# ucurrent.net
KiCad netlist of a schematic drawn in EAGLE
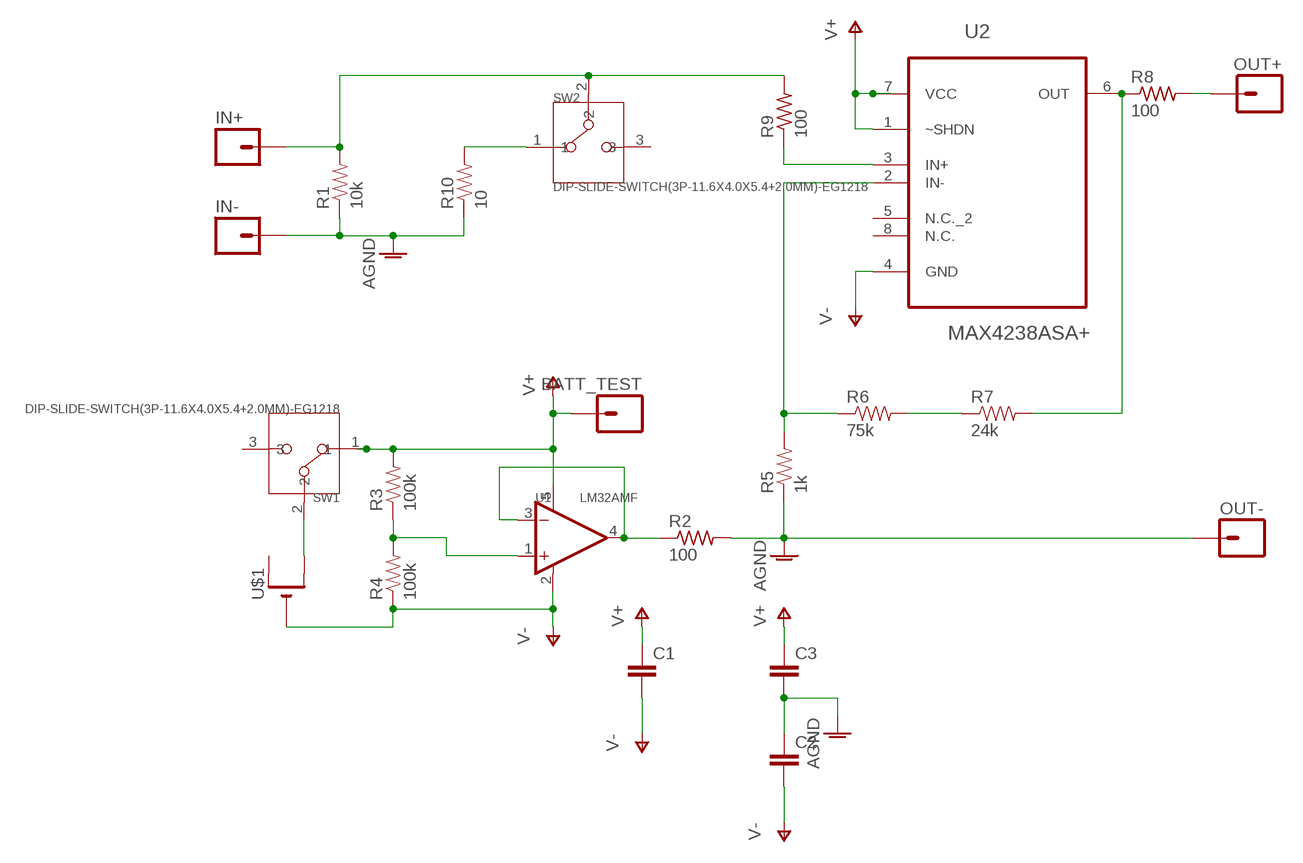
[diagram p0: schematic, sheet 1]

(export (version "E")
  (design (tool "Eeschema 10.0.6"))
  (components
    (comp (ref "BATT_TEST")
      (value "M01PTH_LONGPAD")
      (footprint "eagle-import:1X01_LONGPAD")
      (libsource (lib "eagle-import") (part "M01PTH_LONGPAD"))
    )
    (comp (ref "C1")
      (value "CAP0805")
      (footprint "eagle-import:0805")
      (libsource (lib "eagle-import") (part "CAP0805"))
    )
    (comp (ref "C2")
      (value "CAP0805")
      (footprint "eagle-import:0805")
      (libsource (lib "eagle-import") (part "CAP0805"))
    )
    (comp (ref "C3")
      (value "CAP0805")
      (footprint "eagle-import:0805")
      (libsource (lib "eagle-import") (part "CAP0805"))
    )
    (comp (ref "IN+")
      (value "M01PTH_LONGPAD")
      (footprint "eagle-import:1X01_LONGPAD")
      (libsource (lib "eagle-import") (part "M01PTH_LONGPAD"))
    )
    (comp (ref "IN-")
      (value "M01PTH_LONGPAD")
      (footprint "eagle-import:1X01_LONGPAD")
      (libsource (lib "eagle-import") (part "M01PTH_LONGPAD"))
    )
    (comp (ref "OUT+")
      (value "M01PTH_LONGPAD")
      (footprint "eagle-import:1X01_LONGPAD")
      (libsource (lib "eagle-import") (part "M01PTH_LONGPAD"))
    )
    (comp (ref "OUT-")
      (value "M01PTH_LONGPAD")
      (footprint "eagle-import:1X01_LONGPAD")
      (libsource (lib "eagle-import") (part "M01PTH_LONGPAD"))
    )
    (comp (ref "R1")
      (value "10k")
      (footprint "eagle-import:0805")
      (libsource (lib "eagle-import") (part "RESISTOR0805-RES"))
    )
    (comp (ref "R2")
      (value "100")
      (footprint "eagle-import:0204_7")
      (libsource (lib "eagle-import") (part "R-US_0204/7"))
    )
    (comp (ref "R3")
      (value "100k")
      (footprint "eagle-import:0805")
      (libsource (lib "eagle-import") (part "RESISTOR0805-RES"))
    )
    (comp (ref "R4")
      (value "100k")
      (footprint "eagle-import:0805")
      (libsource (lib "eagle-import") (part "RESISTOR0805-RES"))
    )
    (comp (ref "R5")
      (value "1k")
      (footprint "eagle-import:0805")
      (libsource (lib "eagle-import") (part "RESISTOR0805-RES"))
    )
    (comp (ref "R6")
      (value "75k")
      (footprint "eagle-import:0805")
      (libsource (lib "eagle-import") (part "RESISTOR0805-RES"))
    )
    (comp (ref "R7")
      (value "24k")
      (footprint "eagle-import:0805")
      (libsource (lib "eagle-import") (part "RESISTOR0805-RES"))
    )
    (comp (ref "R8")
      (value "100")
      (footprint "eagle-import:0204_7")
      (libsource (lib "eagle-import") (part "R-US_0204/7"))
    )
    (comp (ref "R9")
      (value "100")
      (footprint "eagle-import:0204_7")
      (libsource (lib "eagle-import") (part "R-US_0204/7"))
    )
    (comp (ref "R10")
      (value "10")
      (footprint "eagle-import:0805")
      (libsource (lib "eagle-import") (part "RESISTOR0805-RES"))
    )
    (comp (ref "SW1")
      (value "DIP-SLIDE-SWITCH(3P-11.6X4.0X5.4+2.0MM)-EG1218")
      (footprint "eagle-import:SW3-2.5-11.6X4.0X5.4+2.0MM")
      (libsource (lib "eagle-import") (part "DIP-SLIDE-SWITCH(3P-11.6X4.0X5.4+2.0MM)-EG1218"))
    )
    (comp (ref "SW2")
      (value "DIP-SLIDE-SWITCH(3P-11.6X4.0X5.4+2.0MM)-EG1218")
      (footprint "eagle-import:SW3-2.5-11.6X4.0X5.4+2.0MM")
      (libsource (lib "eagle-import") (part "DIP-SLIDE-SWITCH(3P-11.6X4.0X5.4+2.0MM)-EG1218"))
    )
    (comp (ref "U$1")
      (value "CR2032SMT")
      (footprint "eagle-import:CR2032-SMD")
      (libsource (lib "eagle-import") (part "CR2032SMT"))
    )
    (comp (ref "U1")
      (value "LM32AMF")
      (footprint "eagle-import:SOT-23-5")
      (fields (field (name "MPN") "LM321MF"))
      (libsource (lib "eagle-import") (part "AMPLIFIER-LM321MF(SOT23-5)"))
    )
    (comp (ref "U2")
      (value "MAX4238ASA+")
      (footprint "eagle-import:SOIC127P600X175-8N")
      (libsource (lib "eagle-import") (part "MAX4238ASA+"))
    )
  )
  (nets
    (net (code "1") (name "AGND") (class "Default")
      (node (ref "C2") (pin "1") (pinfunction "1_1") (pintype "passive"))
      (node (ref "C3") (pin "2") (pinfunction "2_2") (pintype "passive"))
      (node (ref "IN-") (pin "1") (pinfunction "1_1") (pintype "passive"))
      (node (ref "OUT-") (pin "1") (pinfunction "1_1") (pintype "passive"))
      (node (ref "R1") (pin "1") (pinfunction "1_1") (pintype "passive"))
      (node (ref "R10") (pin "1") (pinfunction "1_1") (pintype "passive"))
      (node (ref "R2") (pin "2") (pinfunction "2_2") (pintype "passive"))
      (node (ref "R5") (pin "1") (pinfunction "1_1") (pintype "passive"))
    )
    (net (code "2") (name "Net-(IN+-Pad1)") (class "Default")
      (node (ref "IN+") (pin "1") (pinfunction "1_1") (pintype "passive"))
      (node (ref "R1") (pin "2") (pinfunction "2_2") (pintype "passive"))
      (node (ref "R9") (pin "2") (pinfunction "2_2") (pintype "passive"))
      (node (ref "SW2") (pin "2") (pinfunction "2_2") (pintype "bidirectional"))
    )
    (net (code "3") (name "Net-(OUT+-Pad1)") (class "Default")
      (node (ref "OUT+") (pin "1") (pinfunction "1_1") (pintype "passive"))
      (node (ref "R8") (pin "2") (pinfunction "2_2") (pintype "passive"))
    )
    (net (code "4") (name "Net-(R6-Pad2)") (class "Default")
      (node (ref "R6") (pin "2") (pinfunction "2_2") (pintype "passive"))
      (node (ref "R7") (pin "1") (pinfunction "1_1") (pintype "passive"))
    )
    (net (code "5") (name "Net-(R10-Pad2)") (class "Default")
      (node (ref "R10") (pin "2") (pinfunction "2_2") (pintype "passive"))
      (node (ref "SW2") (pin "1") (pinfunction "1_1") (pintype "bidirectional"))
    )
    (net (code "6") (name "Net-(U$1-+1)") (class "Default")
      (node (ref "SW1") (pin "2") (pinfunction "2_2") (pintype "bidirectional"))
      (node (ref "U$1") (pin "+$2") (pinfunction "+1_+$2") (pintype "passive"))
    )
    (net (code "7") (name "Net-(U1-IN+)") (class "Default")
      (node (ref "R3") (pin "1") (pinfunction "1_1") (pintype "passive"))
      (node (ref "R4") (pin "2") (pinfunction "2_2") (pintype "passive"))
      (node (ref "U1") (pin "1") (pinfunction "IN+_1") (pintype "input"))
    )
    (net (code "8") (name "Net-(U1-IN-)") (class "Default")
      (node (ref "R2") (pin "1") (pinfunction "1_1") (pintype "passive"))
      (node (ref "U1") (pin "3") (pinfunction "IN-_3") (pintype "input"))
      (node (ref "U1") (pin "4") (pinfunction "OUT_4") (pintype "output"))
    )
    (net (code "9") (name "Net-(U2-IN+)") (class "Default")
      (node (ref "R9") (pin "1") (pinfunction "1_1") (pintype "passive"))
      (node (ref "U2") (pin "3") (pinfunction "IN+_3") (pintype "input"))
    )
    (net (code "10") (name "Net-(U2-IN-)") (class "Default")
      (node (ref "R5") (pin "2") (pinfunction "2_2") (pintype "passive"))
      (node (ref "R6") (pin "1") (pinfunction "1_1") (pintype "passive"))
      (node (ref "U2") (pin "2") (pinfunction "IN-_2") (pintype "input"))
    )
    (net (code "11") (name "Net-(U2-OUT)") (class "Default")
      (node (ref "R7") (pin "2") (pinfunction "2_2") (pintype "passive"))
      (node (ref "R8") (pin "1") (pinfunction "1_1") (pintype "passive"))
      (node (ref "U2") (pin "6") (pinfunction "OUT_6") (pintype "output"))
    )
    (net (code "12") (name "V+") (class "Default")
      (node (ref "BATT_TEST") (pin "1") (pinfunction "1_1") (pintype "passive"))
      (node (ref "C1") (pin "1") (pinfunction "1_1") (pintype "passive"))
      (node (ref "C3") (pin "1") (pinfunction "1_1") (pintype "passive"))
      (node (ref "R3") (pin "2") (pinfunction "2_2") (pintype "passive"))
      (node (ref "SW1") (pin "1") (pinfunction "1_1") (pintype "bidirectional"))
      (node (ref "U1") (pin "5") (pinfunction "V+_5") (pintype "power_in"))
      (node (ref "U2") (pin "1") (pinfunction "~{SHDN}_1") (pintype "input"))
      (node (ref "U2") (pin "7") (pinfunction "VCC_7") (pintype "power_in"))
    )
    (net (code "13") (name "V-") (class "Default")
      (node (ref "C1") (pin "2") (pinfunction "2_2") (pintype "passive"))
      (node (ref "C2") (pin "2") (pinfunction "2_2") (pintype "passive"))
      (node (ref "R4") (pin "1") (pinfunction "1_1") (pintype "passive"))
      (node (ref "U$1") (pin "-") (pinfunction "-_-") (pintype "passive"))
      (node (ref "U1") (pin "2") (pinfunction "V-_2") (pintype "power_in"))
      (node (ref "U2") (pin "4") (pinfunction "GND_4") (pintype "passive"))
    )
    (net (code "14") (name "unconnected-(SW1-Pad3)") (class "Default")
      (node (ref "SW1") (pin "3") (pinfunction "3_3") (pintype "bidirectional"))
    )
    (net (code "15") (name "unconnected-(SW2-Pad3)") (class "Default")
      (node (ref "SW2") (pin "3") (pinfunction "3_3") (pintype "bidirectional"))
    )
    (net (code "16") (name "unconnected-(U$1-+-Pad+$1)") (class "Default")
      (node (ref "U$1") (pin "+$1") (pinfunction "+_+$1") (pintype "passive"))
    )
    (net (code "17") (name "unconnected-(U2-N.C.-Pad8)") (class "Default")
      (node (ref "U2") (pin "8") (pinfunction "N.C._8") (pintype "no_connect"))
    )
    (net (code "18") (name "unconnected-(U2-N.C._2-Pad5)") (class "Default")
      (node (ref "U2") (pin "5") (pinfunction "N.C._2_5") (pintype "no_connect"))
    )
  )
)
